# Temp_Sensor.net
KiCad netlist of a schematic drawn in Altium Designer
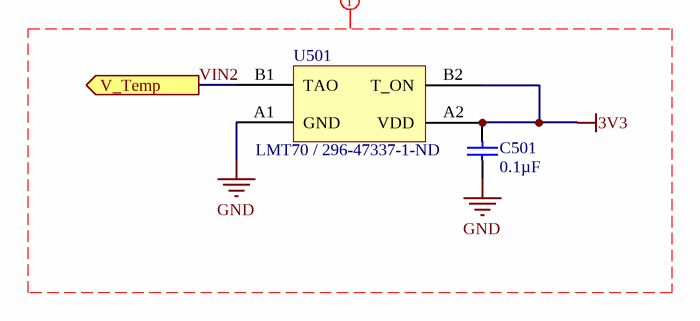
[diagram p0: Temp_Sensor.SchDoc]

(export (version "E")
  (design (tool "Eeschema 10.0.6"))
  (components
    (comp (ref "C501")
      (value "0.1µF")
      (footprint "TDK-CGA2B")
      (description "CAP CER 0.1UF 50V X7R 0402")
      (fields
        (field (name "PART NUMBER") "PC-TDK-02259")
        (field (name "MANUFACTURER PART NUMBER") "CGA2B3X7R1H104K050BB")
        (field (name "PUBLISHER") "AlbertaSat")
      )
      (libsource (lib "Database") (part "Cap"))
    )
    (comp (ref "U501")
      (value "LMT70 / 296-47337-1-ND")
      (footprint "TI-YFQ0004")
      (description "Temperature Sensor Analog, Local -55°C ~ 150°C 5.194mV/°C 4-DSBGA (0.81x0.81)")
      (fields (field (name "PART NUMBER") "70") (field (name "MANUFACTURER PART NUMBER") "LMT70YFQR"))
      (libsource (lib "Database") (part "LMT70"))
    )
  )
  (nets
    (net (code "1") (name "/VIN2") (class "Default")
      (node (ref "U501") (pin "B1") (pinfunction "TAO_B1") (pintype "passive"))
    )
    (net (code "2") (name "3V3") (class "Default")
      (node (ref "C501") (pin "2") (pinfunction "2_2") (pintype "passive"))
      (node (ref "U501") (pin "A2") (pinfunction "VDD_A2") (pintype "passive"))
      (node (ref "U501") (pin "B2") (pinfunction "T_ON_B2") (pintype "passive"))
    )
    (net (code "3") (name "GND") (class "Default")
      (node (ref "C501") (pin "1") (pinfunction "1_1") (pintype "passive"))
      (node (ref "U501") (pin "A1") (pinfunction "GND_A1") (pintype "passive"))
    )
  )
)
